# smart_prototyping.net
KiCad netlist of a schematic drawn in EAGLE
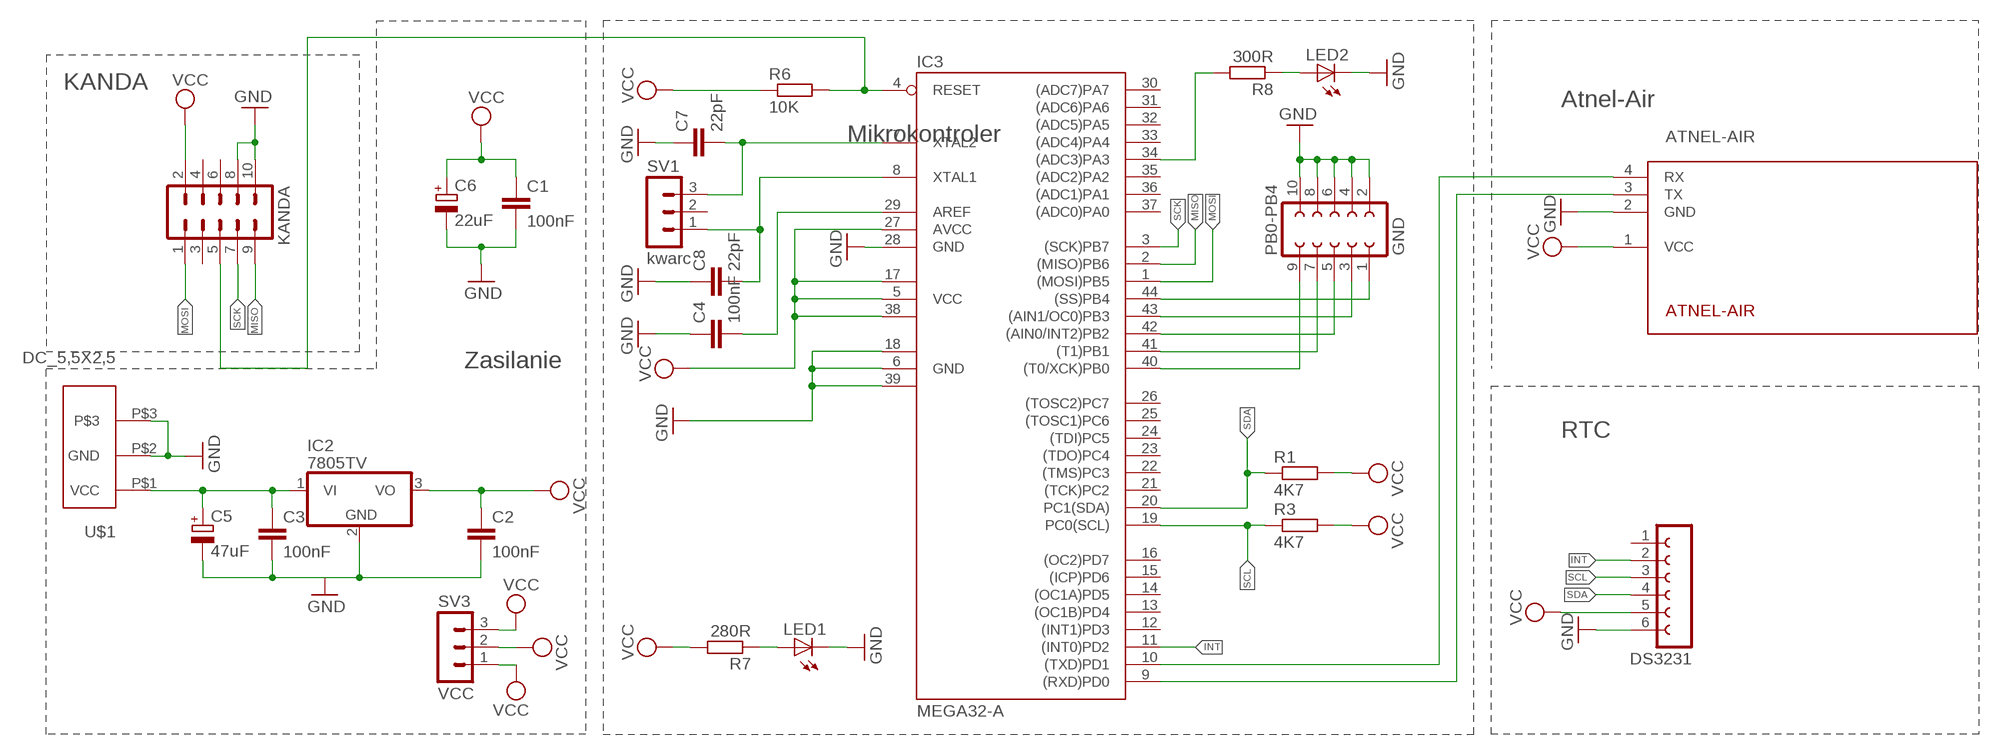
[diagram p0: schematic, sheet 1]

(export (version "E")
  (design (tool "Eeschema 10.0.6"))
  (components
    (comp (ref "ATNEL-AIR")
      (value "ATNEL-AIR")
      (footprint "eagle-import:ATNEL-AIR")
      (libsource (lib "eagle-import") (part "ATNEL-AIR"))
    )
    (comp (ref "C1")
      (value "100nF")
      (footprint "eagle-import:C025-024X044")
      (libsource (lib "eagle-import") (part "C-EU025-024X044"))
    )
    (comp (ref "C2")
      (value "100nF")
      (footprint "eagle-import:C025-024X044")
      (libsource (lib "eagle-import") (part "C-EU025-024X044"))
    )
    (comp (ref "C3")
      (value "100nF")
      (footprint "eagle-import:C025-024X044")
      (libsource (lib "eagle-import") (part "C-EU025-024X044"))
    )
    (comp (ref "C4")
      (value "100nF")
      (footprint "eagle-import:C025-024X044")
      (libsource (lib "eagle-import") (part "C-EU025-024X044"))
    )
    (comp (ref "C5")
      (value "47uF")
      (footprint "eagle-import:B45181A")
      (libsource (lib "eagle-import") (part "CPOL-EUB45181A"))
    )
    (comp (ref "C6")
      (value "22uF")
      (footprint "eagle-import:B45181A")
      (libsource (lib "eagle-import") (part "CPOL-EUB45181A"))
    )
    (comp (ref "C7")
      (value "22pF")
      (footprint "eagle-import:C025-024X044")
      (libsource (lib "eagle-import") (part "C-EU025-024X044"))
    )
    (comp (ref "C8")
      (value "22pF")
      (footprint "eagle-import:C025-024X044")
      (libsource (lib "eagle-import") (part "C-EU025-024X044"))
    )
    (comp (ref "DS3231")
      (value "FE06-1")
      (footprint "eagle-import:FE06")
      (libsource (lib "eagle-import") (part "FE06-1"))
    )
    (comp (ref "IC2")
      (value "7805TV")
      (footprint "eagle-import:TO220V")
      (libsource (lib "eagle-import") (part "78TV05"))
    )
    (comp (ref "IC3")
      (value "MEGA32-A")
      (footprint "eagle-import:TQFP44")
      (fields (field (name "MPN") "ATMEGA32-16AU"))
      (libsource (lib "eagle-import") (part "MEGA32-A"))
    )
    (comp (ref "KANDA")
      (value "ML10")
      (footprint "eagle-import:ML10")
      (libsource (lib "eagle-import") (part "ML10"))
    )
    (comp (ref "LED1")
      (value "LED5MM")
      (footprint "eagle-import:LED5MM")
      (libsource (lib "eagle-import") (part "LED5MM"))
    )
    (comp (ref "LED2")
      (value "LED5MM")
      (footprint "eagle-import:LED5MM")
      (libsource (lib "eagle-import") (part "LED5MM"))
    )
    (comp (ref "PB0-PB4")
      (value "GND")
      (footprint "eagle-import:FE05-2")
      (libsource (lib "eagle-import") (part "FE05-2"))
    )
    (comp (ref "R1")
      (value "4K7")
      (footprint "eagle-import:R1206W")
      (libsource (lib "eagle-import") (part "R-EU_R1206W"))
    )
    (comp (ref "R3")
      (value "4K7")
      (footprint "eagle-import:R1206W")
      (libsource (lib "eagle-import") (part "R-EU_R1206W"))
    )
    (comp (ref "R6")
      (value "10K")
      (footprint "eagle-import:R1206W")
      (libsource (lib "eagle-import") (part "R-EU_R1206W"))
    )
    (comp (ref "R7")
      (value "280R")
      (footprint "eagle-import:R1206W")
      (libsource (lib "eagle-import") (part "R-EU_R1206W"))
    )
    (comp (ref "R8")
      (value "300R")
      (footprint "eagle-import:R1206W")
      (libsource (lib "eagle-import") (part "R-EU_R1206W"))
    )
    (comp (ref "SV1")
      (value "kwarc")
      (footprint "eagle-import:MA03-1")
      (libsource (lib "eagle-import") (part "MA03-1"))
    )
    (comp (ref "SV3")
      (value "VCC")
      (footprint "eagle-import:MA03-1")
      (libsource (lib "eagle-import") (part "MA03-1"))
    )
    (comp (ref "U$1")
      (value "DC_5,5X2,5")
      (footprint "eagle-import:DC_5,5X2,5")
      (libsource (lib "eagle-import") (part "DC_5,5X2,5"))
    )
  )
  (nets
    (net (code "1") (name "GND") (class "Default")
      (node (ref "ATNEL-AIR") (pin "2") (pinfunction "GND_2") (pintype "bidirectional"))
      (node (ref "C1") (pin "2") (pinfunction "2_2") (pintype "passive"))
      (node (ref "C2") (pin "2") (pinfunction "2_2") (pintype "passive"))
      (node (ref "C3") (pin "2") (pinfunction "2_2") (pintype "passive"))
      (node (ref "C4") (pin "1") (pinfunction "1_1") (pintype "passive"))
      (node (ref "C5") (pin "-") (pinfunction "-_-") (pintype "passive"))
      (node (ref "C6") (pin "-") (pinfunction "-_-") (pintype "passive"))
      (node (ref "C7") (pin "1") (pinfunction "1_1") (pintype "passive"))
      (node (ref "C8") (pin "1") (pinfunction "1_1") (pintype "passive"))
      (node (ref "DS3231") (pin "6") (pinfunction "6_6") (pintype "passive"))
      (node (ref "IC2") (pin "2") (pinfunction "GND_2") (pintype "passive"))
      (node (ref "IC3") (pin "18") (pinfunction "GND1_18") (pintype "power_in"))
      (node (ref "IC3") (pin "28") (pinfunction "GND_28") (pintype "power_in"))
      (node (ref "IC3") (pin "39") (pinfunction "GND2_39") (pintype "power_in"))
      (node (ref "IC3") (pin "6") (pinfunction "GND_6") (pintype "power_in"))
      (node (ref "KANDA") (pin "10") (pinfunction "10_10") (pintype "passive"))
      (node (ref "KANDA") (pin "8") (pinfunction "8_8") (pintype "passive"))
      (node (ref "LED1") (pin "K") (pinfunction "C_K") (pintype "passive"))
      (node (ref "LED2") (pin "K") (pinfunction "C_K") (pintype "passive"))
      (node (ref "PB0-PB4") (pin "10") (pinfunction "10_10") (pintype "passive"))
      (node (ref "PB0-PB4") (pin "2") (pinfunction "2_2") (pintype "passive"))
      (node (ref "PB0-PB4") (pin "4") (pinfunction "4_4") (pintype "passive"))
      (node (ref "PB0-PB4") (pin "6") (pinfunction "6_6") (pintype "passive"))
      (node (ref "PB0-PB4") (pin "8") (pinfunction "8_8") (pintype "passive"))
      (node (ref "U$1") (pin "P$2") (pinfunction "GND_P$2") (pintype "bidirectional"))
      (node (ref "U$1") (pin "P$3") (pinfunction "P$3_P$3") (pintype "bidirectional"))
    )
    (net (code "2") (name "INT") (class "Default")
      (node (ref "DS3231") (pin "2") (pinfunction "2_2") (pintype "passive"))
      (node (ref "IC3") (pin "11") (pinfunction "(INT0)PD2_11") (pintype "bidirectional"))
    )
    (net (code "3") (name "MISO") (class "Default")
      (node (ref "IC3") (pin "2") (pinfunction "(MISO)PB6_2") (pintype "bidirectional"))
      (node (ref "KANDA") (pin "9") (pinfunction "9_9") (pintype "passive"))
    )
    (net (code "4") (name "MOSI") (class "Default")
      (node (ref "IC3") (pin "1") (pinfunction "(MOSI)PB5_1") (pintype "bidirectional"))
      (node (ref "KANDA") (pin "1") (pinfunction "1_1") (pintype "passive"))
    )
    (net (code "5") (name "Net-(ATNEL-AIR-RX)") (class "Default")
      (node (ref "ATNEL-AIR") (pin "4") (pinfunction "RX_4") (pintype "output"))
      (node (ref "IC3") (pin "10") (pinfunction "(TXD)PD1_10") (pintype "bidirectional"))
    )
    (net (code "6") (name "Net-(ATNEL-AIR-TX)") (class "Default")
      (node (ref "ATNEL-AIR") (pin "3") (pinfunction "TX_3") (pintype "input"))
      (node (ref "IC3") (pin "9") (pinfunction "(RXD)PD0_9") (pintype "bidirectional"))
    )
    (net (code "7") (name "Net-(IC2-VI)") (class "Default")
      (node (ref "C3") (pin "1") (pinfunction "1_1") (pintype "passive"))
      (node (ref "C5") (pin "+") (pinfunction "+_+") (pintype "passive"))
      (node (ref "IC2") (pin "1") (pinfunction "VI_1") (pintype "input"))
      (node (ref "U$1") (pin "P$1") (pinfunction "VCC_P$1") (pintype "bidirectional"))
    )
    (net (code "8") (name "Net-(IC3-(ADC3)PA3)") (class "Default")
      (node (ref "IC3") (pin "34") (pinfunction "(ADC3)PA3_34") (pintype "bidirectional"))
      (node (ref "R8") (pin "2") (pinfunction "2_2") (pintype "passive"))
    )
    (net (code "9") (name "Net-(IC3-(AIN0{slash}INT2)PB2)") (class "Default")
      (node (ref "IC3") (pin "42") (pinfunction "(AIN0/INT2)PB2_42") (pintype "bidirectional"))
      (node (ref "PB0-PB4") (pin "5") (pinfunction "5_5") (pintype "passive"))
    )
    (net (code "10") (name "Net-(IC3-(AIN1{slash}OC0)PB3)") (class "Default")
      (node (ref "IC3") (pin "43") (pinfunction "(AIN1/OC0)PB3_43") (pintype "bidirectional"))
      (node (ref "PB0-PB4") (pin "3") (pinfunction "3_3") (pintype "passive"))
    )
    (net (code "11") (name "Net-(IC3-(SS)PB4)") (class "Default")
      (node (ref "IC3") (pin "44") (pinfunction "(SS)PB4_44") (pintype "bidirectional"))
      (node (ref "PB0-PB4") (pin "1") (pinfunction "1_1") (pintype "passive"))
    )
    (net (code "12") (name "Net-(IC3-(T0{slash}XCK)PB0)") (class "Default")
      (node (ref "IC3") (pin "40") (pinfunction "(T0/XCK)PB0_40") (pintype "bidirectional"))
      (node (ref "PB0-PB4") (pin "9") (pinfunction "9_9") (pintype "passive"))
    )
    (net (code "13") (name "Net-(IC3-(T1)PB1)") (class "Default")
      (node (ref "IC3") (pin "41") (pinfunction "(T1)PB1_41") (pintype "bidirectional"))
      (node (ref "PB0-PB4") (pin "7") (pinfunction "7_7") (pintype "passive"))
    )
    (net (code "14") (name "Net-(IC3-AREF)") (class "Default")
      (node (ref "C4") (pin "2") (pinfunction "2_2") (pintype "passive"))
      (node (ref "IC3") (pin "29") (pinfunction "AREF_29") (pintype "passive"))
    )
    (net (code "15") (name "Net-(IC3-RESET)") (class "Default")
      (node (ref "IC3") (pin "4") (pinfunction "RESET_4") (pintype "input"))
      (node (ref "KANDA") (pin "5") (pinfunction "5_5") (pintype "passive"))
      (node (ref "R6") (pin "2") (pinfunction "2_2") (pintype "passive"))
    )
    (net (code "16") (name "Net-(IC3-XTAL1)") (class "Default")
      (node (ref "C8") (pin "2") (pinfunction "2_2") (pintype "passive"))
      (node (ref "IC3") (pin "8") (pinfunction "XTAL1_8") (pintype "bidirectional"))
      (node (ref "SV1") (pin "1") (pinfunction "1_1") (pintype "passive"))
    )
    (net (code "17") (name "Net-(IC3-XTAL2)") (class "Default")
      (node (ref "C7") (pin "2") (pinfunction "2_2") (pintype "passive"))
      (node (ref "IC3") (pin "7") (pinfunction "XTAL2_7") (pintype "bidirectional"))
      (node (ref "SV1") (pin "3") (pinfunction "3_3") (pintype "passive"))
    )
    (net (code "18") (name "Net-(LED1-PadA)") (class "Default")
      (node (ref "LED1") (pin "A") (pinfunction "A_A") (pintype "passive"))
      (node (ref "R7") (pin "1") (pinfunction "1_1") (pintype "passive"))
    )
    (net (code "19") (name "Net-(LED2-PadA)") (class "Default")
      (node (ref "LED2") (pin "A") (pinfunction "A_A") (pintype "passive"))
      (node (ref "R8") (pin "1") (pinfunction "1_1") (pintype "passive"))
    )
    (net (code "20") (name "SCK") (class "Default")
      (node (ref "IC3") (pin "3") (pinfunction "(SCK)PB7_3") (pintype "bidirectional"))
      (node (ref "KANDA") (pin "7") (pinfunction "7_7") (pintype "passive"))
    )
    (net (code "21") (name "SCL") (class "Default")
      (node (ref "DS3231") (pin "3") (pinfunction "3_3") (pintype "passive"))
      (node (ref "IC3") (pin "19") (pinfunction "PC0(SCL)_19") (pintype "bidirectional"))
      (node (ref "R3") (pin "1") (pinfunction "1_1") (pintype "passive"))
    )
    (net (code "22") (name "SDA") (class "Default")
      (node (ref "DS3231") (pin "4") (pinfunction "4_4") (pintype "passive"))
      (node (ref "IC3") (pin "20") (pinfunction "PC1(SDA)_20") (pintype "bidirectional"))
      (node (ref "R1") (pin "1") (pinfunction "1_1") (pintype "passive"))
    )
    (net (code "23") (name "VCC") (class "Default")
      (node (ref "ATNEL-AIR") (pin "1") (pinfunction "VCC_1") (pintype "bidirectional"))
      (node (ref "C1") (pin "1") (pinfunction "1_1") (pintype "passive"))
      (node (ref "C2") (pin "1") (pinfunction "1_1") (pintype "passive"))
      (node (ref "C6") (pin "+") (pinfunction "+_+") (pintype "passive"))
      (node (ref "DS3231") (pin "5") (pinfunction "5_5") (pintype "passive"))
      (node (ref "IC2") (pin "3") (pinfunction "VO_3") (pintype "passive"))
      (node (ref "IC3") (pin "17") (pinfunction "VCC1_17") (pintype "power_in"))
      (node (ref "IC3") (pin "27") (pinfunction "AVCC_27") (pintype "power_in"))
      (node (ref "IC3") (pin "38") (pinfunction "VCC2_38") (pintype "power_in"))
      (node (ref "IC3") (pin "5") (pinfunction "VCC_5") (pintype "power_in"))
      (node (ref "KANDA") (pin "2") (pinfunction "2_2") (pintype "passive"))
      (node (ref "R1") (pin "2") (pinfunction "2_2") (pintype "passive"))
      (node (ref "R3") (pin "2") (pinfunction "2_2") (pintype "passive"))
      (node (ref "R6") (pin "1") (pinfunction "1_1") (pintype "passive"))
      (node (ref "R7") (pin "2") (pinfunction "2_2") (pintype "passive"))
      (node (ref "SV3") (pin "1") (pinfunction "1_1") (pintype "passive"))
      (node (ref "SV3") (pin "2") (pinfunction "2_2") (pintype "passive"))
      (node (ref "SV3") (pin "3") (pinfunction "3_3") (pintype "passive"))
    )
    (net (code "24") (name "unconnected-(DS3231-Pad1)") (class "Default")
      (node (ref "DS3231") (pin "1") (pinfunction "1_1") (pintype "passive"))
    )
    (net (code "25") (name "unconnected-(IC3-(ADC0)PA0-Pad37)") (class "Default")
      (node (ref "IC3") (pin "37") (pinfunction "(ADC0)PA0_37") (pintype "bidirectional"))
    )
    (net (code "26") (name "unconnected-(IC3-(ADC1)PA1-Pad36)") (class "Default")
      (node (ref "IC3") (pin "36") (pinfunction "(ADC1)PA1_36") (pintype "bidirectional"))
    )
    (net (code "27") (name "unconnected-(IC3-(ADC2)PA2-Pad35)") (class "Default")
      (node (ref "IC3") (pin "35") (pinfunction "(ADC2)PA2_35") (pintype "bidirectional"))
    )
    (net (code "28") (name "unconnected-(IC3-(ADC4)PA4-Pad33)") (class "Default")
      (node (ref "IC3") (pin "33") (pinfunction "(ADC4)PA4_33") (pintype "bidirectional"))
    )
    (net (code "29") (name "unconnected-(IC3-(ADC5)PA5-Pad32)") (class "Default")
      (node (ref "IC3") (pin "32") (pinfunction "(ADC5)PA5_32") (pintype "bidirectional"))
    )
    (net (code "30") (name "unconnected-(IC3-(ADC6)PA6-Pad31)") (class "Default")
      (node (ref "IC3") (pin "31") (pinfunction "(ADC6)PA6_31") (pintype "bidirectional"))
    )
    (net (code "31") (name "unconnected-(IC3-(ADC7)PA7-Pad30)") (class "Default")
      (node (ref "IC3") (pin "30") (pinfunction "(ADC7)PA7_30") (pintype "bidirectional"))
    )
    (net (code "32") (name "unconnected-(IC3-(ICP)PD6-Pad15)") (class "Default")
      (node (ref "IC3") (pin "15") (pinfunction "(ICP)PD6_15") (pintype "bidirectional"))
    )
    (net (code "33") (name "unconnected-(IC3-(INT1)PD3-Pad12)") (class "Default")
      (node (ref "IC3") (pin "12") (pinfunction "(INT1)PD3_12") (pintype "bidirectional"))
    )
    (net (code "34") (name "unconnected-(IC3-(OC1A)PD5-Pad14)") (class "Default")
      (node (ref "IC3") (pin "14") (pinfunction "(OC1A)PD5_14") (pintype "bidirectional"))
    )
    (net (code "35") (name "unconnected-(IC3-(OC1B)PD4-Pad13)") (class "Default")
      (node (ref "IC3") (pin "13") (pinfunction "(OC1B)PD4_13") (pintype "bidirectional"))
    )
    (net (code "36") (name "unconnected-(IC3-(OC2)PD7-Pad16)") (class "Default")
      (node (ref "IC3") (pin "16") (pinfunction "(OC2)PD7_16") (pintype "bidirectional"))
    )
    (net (code "37") (name "unconnected-(IC3-(TCK)PC2-Pad21)") (class "Default")
      (node (ref "IC3") (pin "21") (pinfunction "(TCK)PC2_21") (pintype "bidirectional"))
    )
    (net (code "38") (name "unconnected-(IC3-(TDI)PC5-Pad24)") (class "Default")
      (node (ref "IC3") (pin "24") (pinfunction "(TDI)PC5_24") (pintype "bidirectional"))
    )
    (net (code "39") (name "unconnected-(IC3-(TDO)PC4-Pad23)") (class "Default")
      (node (ref "IC3") (pin "23") (pinfunction "(TDO)PC4_23") (pintype "bidirectional"))
    )
    (net (code "40") (name "unconnected-(IC3-(TMS)PC3-Pad22)") (class "Default")
      (node (ref "IC3") (pin "22") (pinfunction "(TMS)PC3_22") (pintype "bidirectional"))
    )
    (net (code "41") (name "unconnected-(IC3-(TOSC1)PC6-Pad25)") (class "Default")
      (node (ref "IC3") (pin "25") (pinfunction "(TOSC1)PC6_25") (pintype "bidirectional"))
    )
    (net (code "42") (name "unconnected-(IC3-(TOSC2)PC7-Pad26)") (class "Default")
      (node (ref "IC3") (pin "26") (pinfunction "(TOSC2)PC7_26") (pintype "bidirectional"))
    )
    (net (code "43") (name "unconnected-(KANDA-Pad3)") (class "Default")
      (node (ref "KANDA") (pin "3") (pinfunction "3_3") (pintype "passive"))
    )
    (net (code "44") (name "unconnected-(KANDA-Pad4)") (class "Default")
      (node (ref "KANDA") (pin "4") (pinfunction "4_4") (pintype "passive"))
    )
    (net (code "45") (name "unconnected-(KANDA-Pad6)") (class "Default")
      (node (ref "KANDA") (pin "6") (pinfunction "6_6") (pintype "passive"))
    )
    (net (code "46") (name "unconnected-(SV1-Pad2)") (class "Default")
      (node (ref "SV1") (pin "2") (pinfunction "2_2") (pintype "passive"))
    )
  )
)
